# Sensor.net
KiCad netlist of a schematic drawn in EAGLE
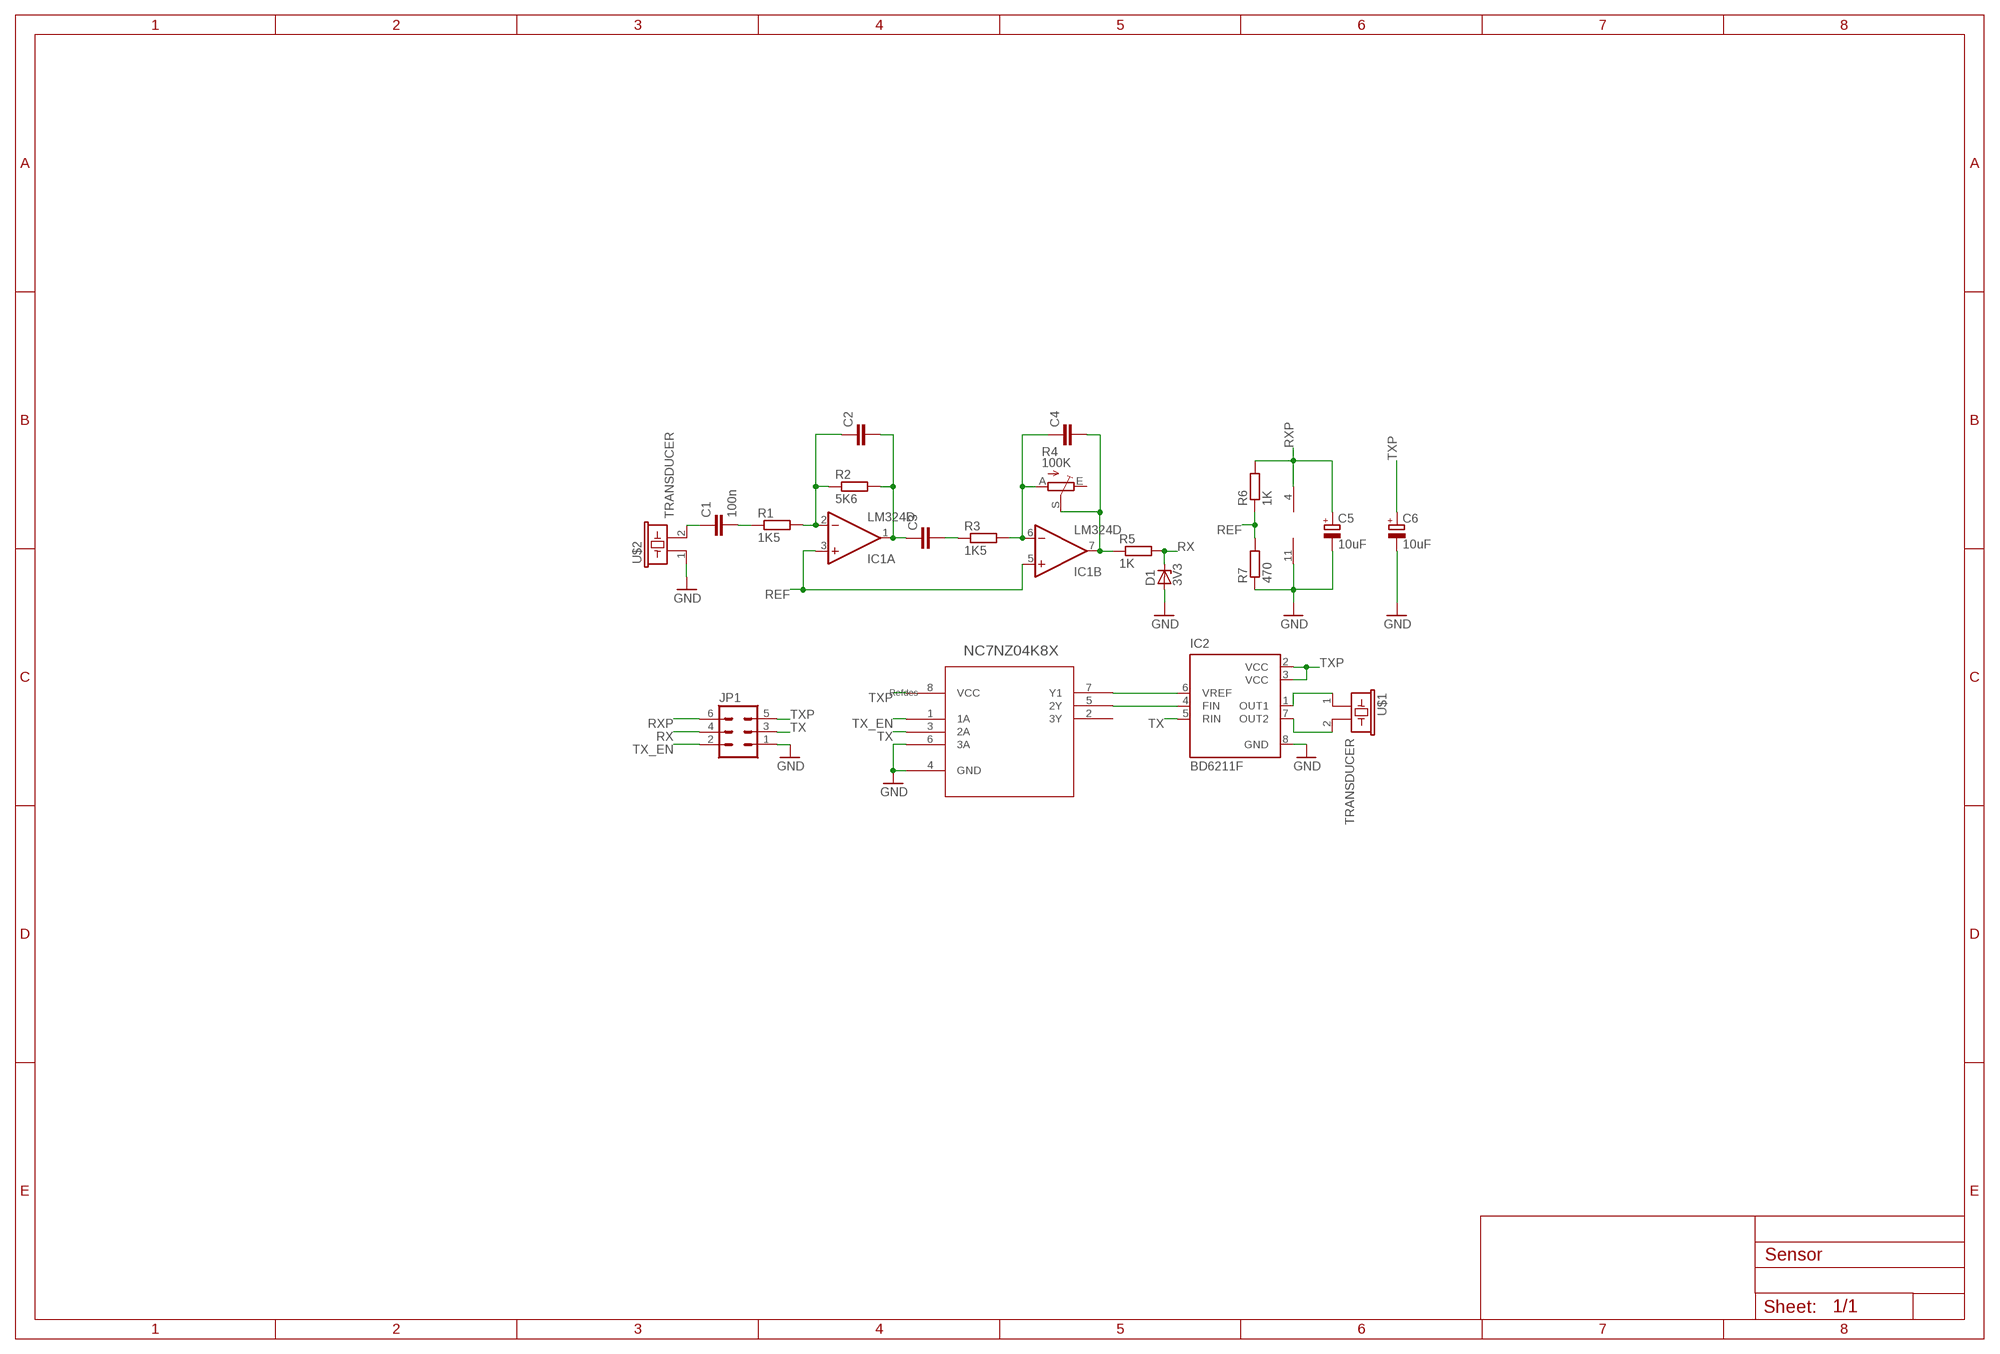
[diagram p0: schematic, sheet 1]

(export (version "E")
  (design (tool "Eeschema 10.0.6"))
  (components
    (comp (ref "C1")
      (value "100n")
      (footprint "eagle-import:C0805")
      (libsource (lib "eagle-import") (part "C-EUC0805"))
    )
    (comp (ref "C2")
      (value "C-EUC0805")
      (footprint "eagle-import:C0805")
      (libsource (lib "eagle-import") (part "C-EUC0805"))
    )
    (comp (ref "C3")
      (value "C-EUC0805")
      (footprint "eagle-import:C0805")
      (libsource (lib "eagle-import") (part "C-EUC0805"))
    )
    (comp (ref "C4")
      (value "C-EUC0805")
      (footprint "eagle-import:C0805")
      (libsource (lib "eagle-import") (part "C-EUC0805"))
    )
    (comp (ref "C5")
      (value "10uF")
      (footprint "eagle-import:E2-5")
      (libsource (lib "eagle-import") (part "CPOL-EUE2-5"))
    )
    (comp (ref "C6")
      (value "10uF")
      (footprint "eagle-import:E2-5")
      (libsource (lib "eagle-import") (part "CPOL-EUE2-5"))
    )
    (comp (ref "D1")
      (value "3V3")
      (footprint "eagle-import:ZDIO-2.5")
      (libsource (lib "eagle-import") (part "ZENER-DIODEZD-2.5"))
    )
    (comp (ref "IC1")
      (value "LM324D")
      (footprint "eagle-import:SO14")
      (fields (field (name "OC_FARNELL") "1426353"))
      (libsource (lib "eagle-import") (part "LM324D"))
    )
    (comp (ref "IC2")
      (value "BD6211F")
      (footprint "eagle-import:SOP8")
      (libsource (lib "eagle-import") (part "BD6211F"))
    )
    (comp (ref "JP1")
      (value "MA03-2")
      (footprint "eagle-import:MA03-2")
      (libsource (lib "eagle-import") (part "MA03-2"))
    )
    (comp (ref "R1")
      (value "1K5")
      (footprint "eagle-import:R0805")
      (libsource (lib "eagle-import") (part "R-EU_R0805"))
    )
    (comp (ref "R2")
      (value "5K6")
      (footprint "eagle-import:R0805")
      (libsource (lib "eagle-import") (part "R-EU_R0805"))
    )
    (comp (ref "R3")
      (value "1K5")
      (footprint "eagle-import:R0805")
      (libsource (lib "eagle-import") (part "R-EU_R0805"))
    )
    (comp (ref "R4")
      (value "100K")
      (footprint "eagle-import:S63P")
      (libsource (lib "eagle-import") (part "TRIM_EU-S63P"))
    )
    (comp (ref "R5")
      (value "1K")
      (footprint "eagle-import:R0805")
      (libsource (lib "eagle-import") (part "R-EU_R0805"))
    )
    (comp (ref "R6")
      (value "1K")
      (footprint "eagle-import:R0805")
      (libsource (lib "eagle-import") (part "R-EU_R0805"))
    )
    (comp (ref "R7")
      (value "470")
      (footprint "eagle-import:R0805")
      (libsource (lib "eagle-import") (part "R-EU_R0805"))
    )
    (comp (ref "U$1")
      (value "TRANSDUCER")
      (footprint "eagle-import:TRANSDUCER")
      (libsource (lib "eagle-import") (part "TRANSDUCER"))
    )
    (comp (ref "U$2")
      (value "TRANSDUCER")
      (footprint "eagle-import:TRANSDUCER")
      (libsource (lib "eagle-import") (part "TRANSDUCER"))
    )
    (comp (ref "U1")
      (value "NC7NZ04K8X")
      (footprint "eagle-import:SOP50P310X90-8N")
      (libsource (lib "eagle-import") (part "NC7NZ04K8X"))
    )
  )
  (nets
    (net (code "1") (name "/REF") (class "Default")
      (node (ref "IC1") (pin "3") (pinfunction "+IN_3") (pintype "input"))
      (node (ref "IC1") (pin "5") (pinfunction "+IN_5") (pintype "input"))
      (node (ref "R6") (pin "1") (pinfunction "1_1") (pintype "passive"))
      (node (ref "R7") (pin "2") (pinfunction "2_2") (pintype "passive"))
    )
    (net (code "2") (name "/RX") (class "Default")
      (node (ref "D1") (pin "C") (pinfunction "C_C") (pintype "passive"))
      (node (ref "JP1") (pin "4") (pinfunction "4_4") (pintype "passive"))
      (node (ref "R5") (pin "2") (pinfunction "2_2") (pintype "passive"))
    )
    (net (code "3") (name "/RXP") (class "Default")
      (node (ref "C5") (pin "+") (pinfunction "+_+") (pintype "passive"))
      (node (ref "IC1") (pin "4") (pinfunction "V+_4") (pintype "power_in"))
      (node (ref "JP1") (pin "6") (pinfunction "6_6") (pintype "passive"))
      (node (ref "R6") (pin "2") (pinfunction "2_2") (pintype "passive"))
    )
    (net (code "4") (name "/TX") (class "Default")
      (node (ref "IC2") (pin "5") (pinfunction "RIN_5") (pintype "input"))
      (node (ref "JP1") (pin "3") (pinfunction "3_3") (pintype "passive"))
      (node (ref "U1") (pin "3") (pinfunction "2A_3") (pintype "input"))
    )
    (net (code "5") (name "/TXP") (class "Default")
      (node (ref "C6") (pin "+") (pinfunction "+_+") (pintype "passive"))
      (node (ref "IC2") (pin "2") (pinfunction "VCC_2") (pintype "power_in"))
      (node (ref "IC2") (pin "3") (pinfunction "VCC_3") (pintype "power_in"))
      (node (ref "JP1") (pin "5") (pinfunction "5_5") (pintype "passive"))
      (node (ref "U1") (pin "8") (pinfunction "VCC_8") (pintype "power_in"))
    )
    (net (code "6") (name "/TX_EN") (class "Default")
      (node (ref "JP1") (pin "2") (pinfunction "2_2") (pintype "passive"))
      (node (ref "U1") (pin "1") (pinfunction "1A_1") (pintype "input"))
    )
    (net (code "7") (name "GND") (class "Default")
      (node (ref "C5") (pin "-") (pinfunction "-_-") (pintype "passive"))
      (node (ref "C6") (pin "-") (pinfunction "-_-") (pintype "passive"))
      (node (ref "D1") (pin "A") (pinfunction "A_A") (pintype "passive"))
      (node (ref "IC1") (pin "11") (pinfunction "V-_11") (pintype "power_in"))
      (node (ref "IC2") (pin "8") (pinfunction "GND_8") (pintype "power_in"))
      (node (ref "JP1") (pin "1") (pinfunction "1_1") (pintype "passive"))
      (node (ref "R7") (pin "1") (pinfunction "1_1") (pintype "passive"))
      (node (ref "U$2") (pin "1") (pinfunction "1_1") (pintype "passive"))
      (node (ref "U1") (pin "4") (pinfunction "GND_4") (pintype "passive"))
      (node (ref "U1") (pin "6") (pinfunction "3A_6") (pintype "input"))
    )
    (net (code "8") (name "Net-(C1-Pad1)") (class "Default")
      (node (ref "C1") (pin "1") (pinfunction "1_1") (pintype "passive"))
      (node (ref "U$2") (pin "2") (pinfunction "2_2") (pintype "passive"))
    )
    (net (code "9") (name "Net-(C1-Pad2)") (class "Default")
      (node (ref "C1") (pin "2") (pinfunction "2_2") (pintype "passive"))
      (node (ref "R1") (pin "1") (pinfunction "1_1") (pintype "passive"))
    )
    (net (code "10") (name "Net-(C3-Pad2)") (class "Default")
      (node (ref "C3") (pin "2") (pinfunction "2_2") (pintype "passive"))
      (node (ref "R3") (pin "1") (pinfunction "1_1") (pintype "passive"))
    )
    (net (code "11") (name "Net-(IC1A--IN)") (class "Default")
      (node (ref "C2") (pin "1") (pinfunction "1_1") (pintype "passive"))
      (node (ref "IC1") (pin "2") (pinfunction "-IN_2") (pintype "input"))
      (node (ref "R1") (pin "2") (pinfunction "2_2") (pintype "passive"))
      (node (ref "R2") (pin "1") (pinfunction "1_1") (pintype "passive"))
    )
    (net (code "12") (name "Net-(IC1A-OUT)") (class "Default")
      (node (ref "C2") (pin "2") (pinfunction "2_2") (pintype "passive"))
      (node (ref "C3") (pin "1") (pinfunction "1_1") (pintype "passive"))
      (node (ref "IC1") (pin "1") (pinfunction "OUT_1") (pintype "output"))
      (node (ref "R2") (pin "2") (pinfunction "2_2") (pintype "passive"))
    )
    (net (code "13") (name "Net-(IC1B--IN)") (class "Default")
      (node (ref "C4") (pin "1") (pinfunction "1_1") (pintype "passive"))
      (node (ref "IC1") (pin "6") (pinfunction "-IN_6") (pintype "input"))
      (node (ref "R3") (pin "2") (pinfunction "2_2") (pintype "passive"))
      (node (ref "R4") (pin "A") (pinfunction "A_A") (pintype "passive"))
    )
    (net (code "14") (name "Net-(IC1B-OUT)") (class "Default")
      (node (ref "C4") (pin "2") (pinfunction "2_2") (pintype "passive"))
      (node (ref "IC1") (pin "7") (pinfunction "OUT_7") (pintype "output"))
      (node (ref "R4") (pin "S") (pinfunction "S_S") (pintype "passive"))
      (node (ref "R5") (pin "1") (pinfunction "1_1") (pintype "passive"))
    )
    (net (code "15") (name "Net-(IC2-FIN)") (class "Default")
      (node (ref "IC2") (pin "4") (pinfunction "FIN_4") (pintype "input"))
      (node (ref "U1") (pin "5") (pinfunction "2Y_5") (pintype "output"))
    )
    (net (code "16") (name "Net-(IC2-OUT1)") (class "Default")
      (node (ref "IC2") (pin "1") (pinfunction "OUT1_1") (pintype "output"))
      (node (ref "U$1") (pin "1") (pinfunction "1_1") (pintype "passive"))
    )
    (net (code "17") (name "Net-(IC2-OUT2)") (class "Default")
      (node (ref "IC2") (pin "7") (pinfunction "OUT2_7") (pintype "output"))
      (node (ref "U$1") (pin "2") (pinfunction "2_2") (pintype "passive"))
    )
    (net (code "18") (name "Net-(IC2-VREF)") (class "Default")
      (node (ref "IC2") (pin "6") (pinfunction "VREF_6") (pintype "passive"))
      (node (ref "U1") (pin "7") (pinfunction "Y1_7") (pintype "output"))
    )
    (net (code "19") (name "unconnected-(R4-PadE)") (class "Default")
      (node (ref "R4") (pin "E") (pinfunction "E_E") (pintype "passive"))
    )
    (net (code "20") (name "unconnected-(U1-3Y-Pad2)") (class "Default")
      (node (ref "U1") (pin "2") (pinfunction "3Y_2") (pintype "output"))
    )
  )
)
